# 1-Schematic_LP2951-xx_Matrix_Test_Board.net
KiCad netlist of a schematic drawn in EasyEDA
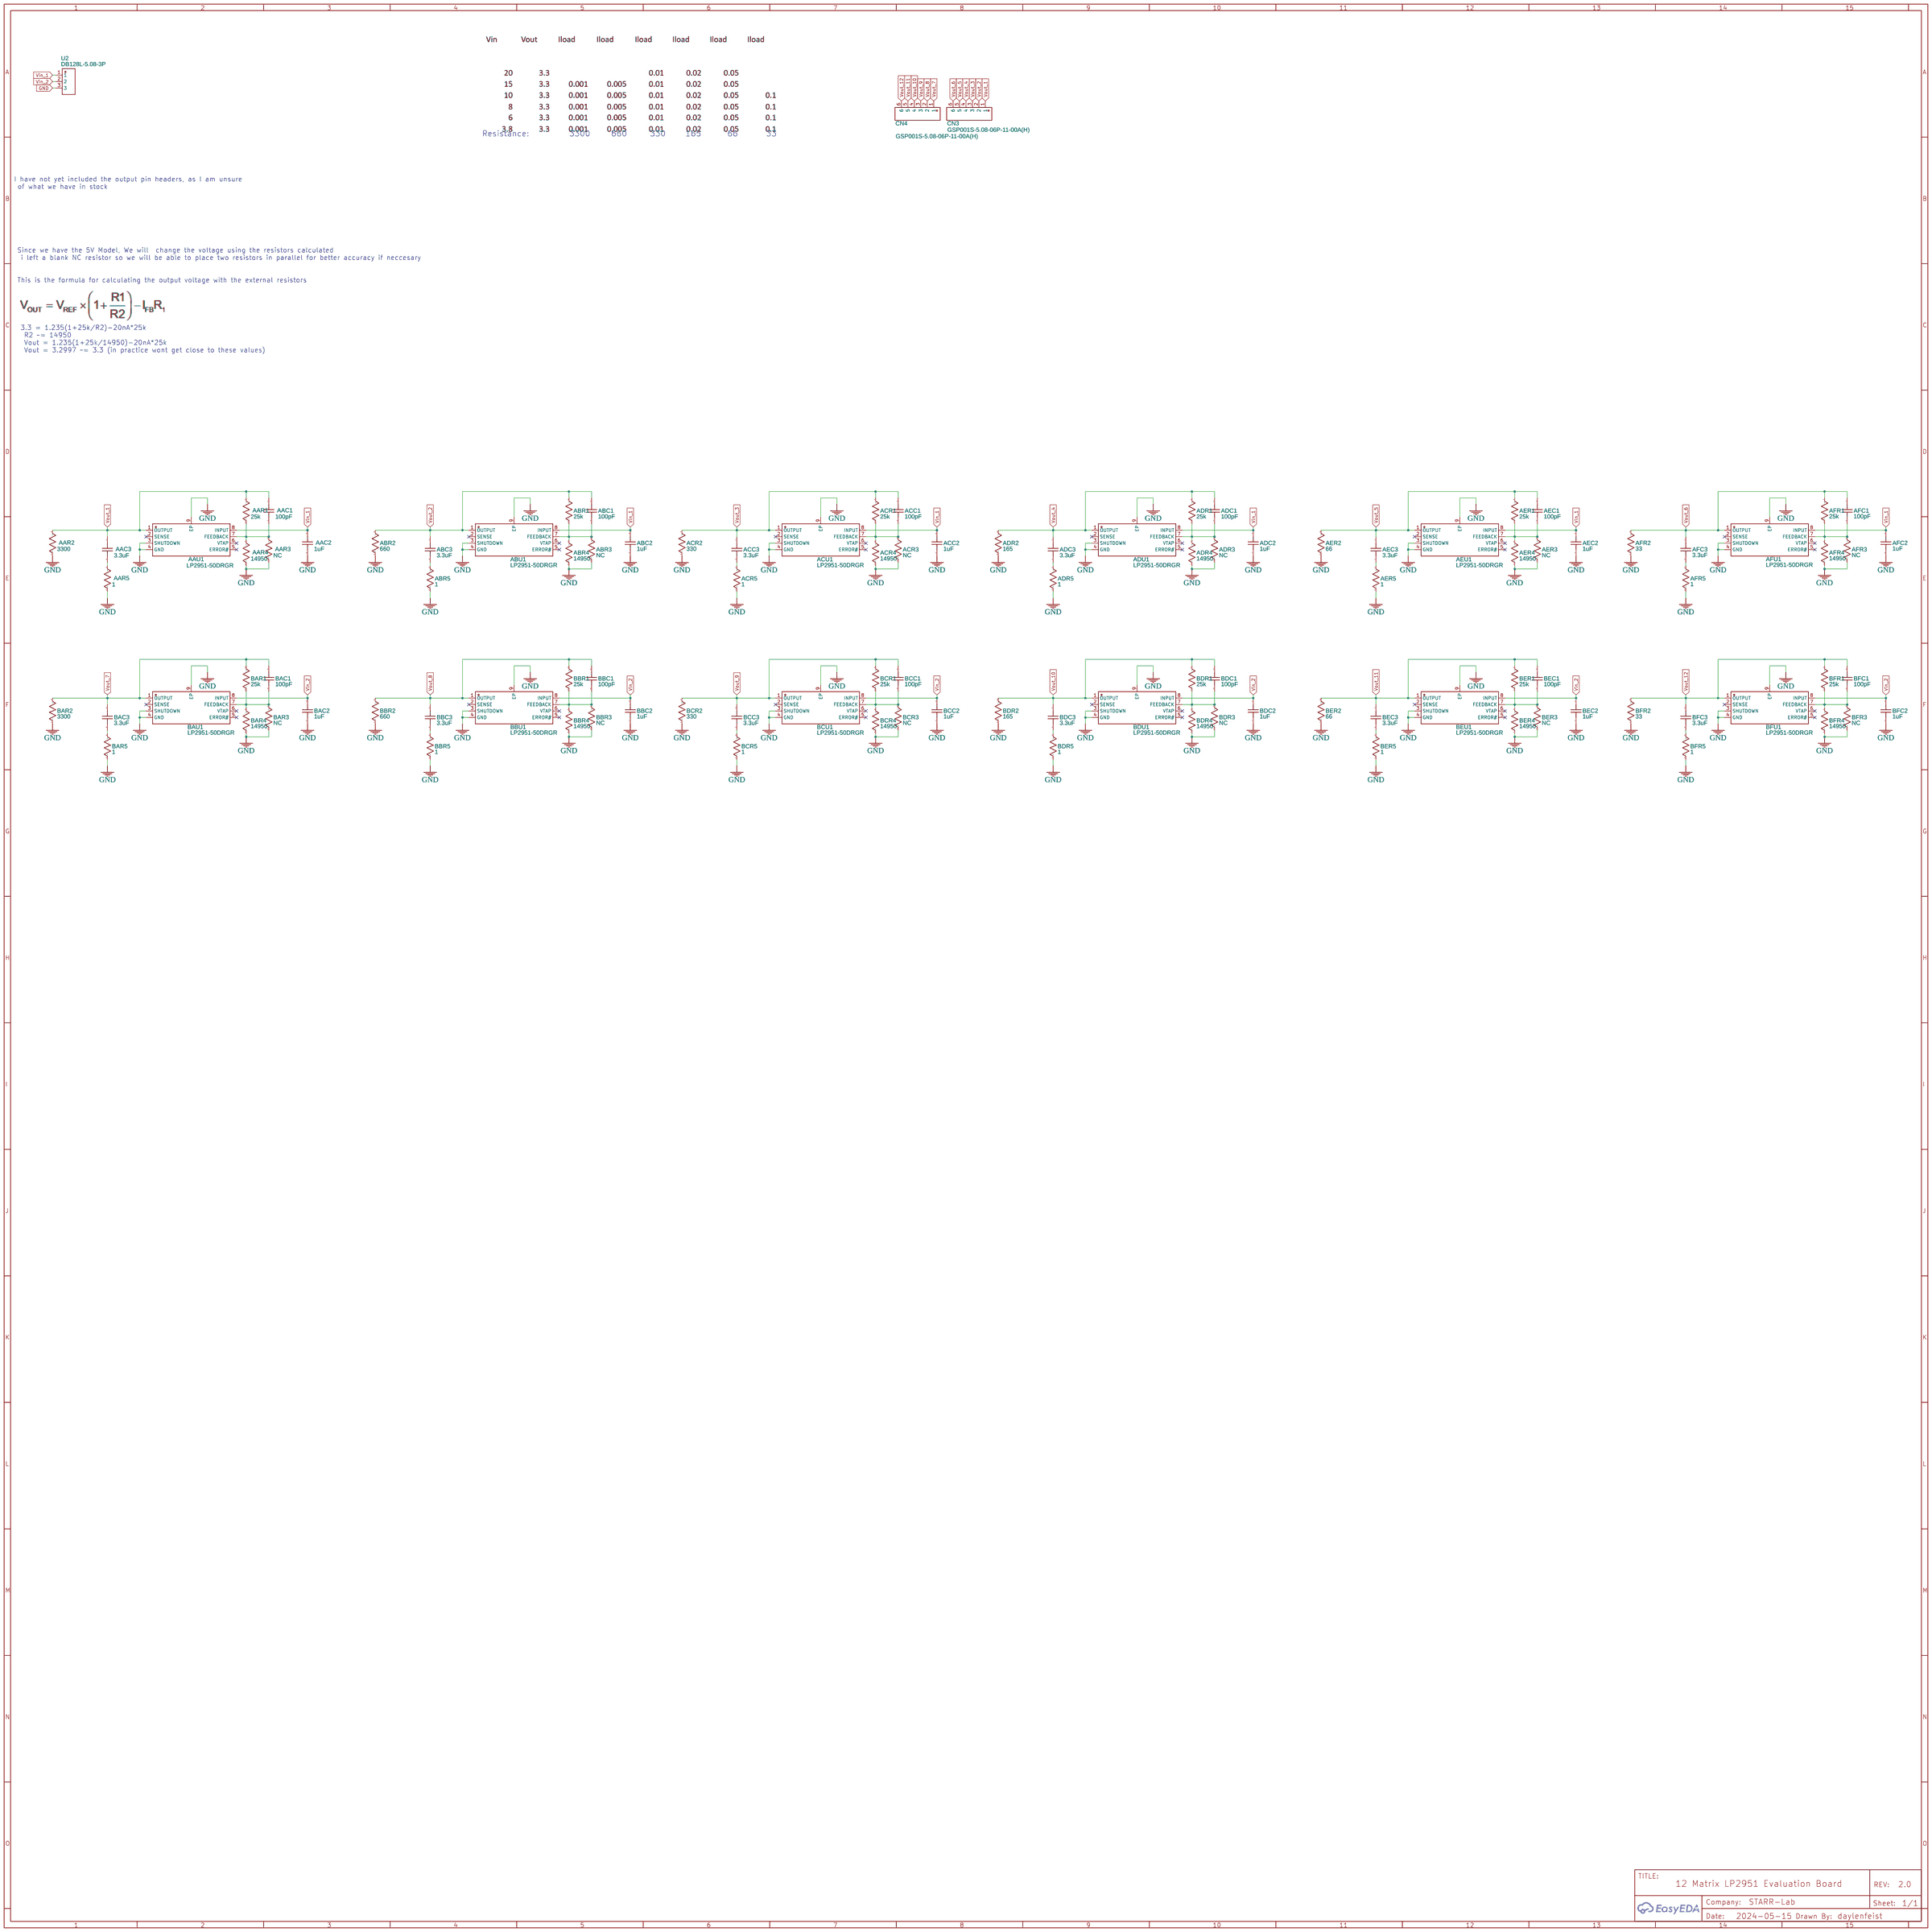
[diagram p0: schematic sheet]

(export (version "E")
  (design (tool "Eeschema 10.0.6"))
  (components
    (comp (ref "AAC1") (value "100pF") (libsource (lib "") (part "C_0603_US")))
    (comp (ref "AAC2") (value "1uF") (libsource (lib "") (part "C_0603_US_13")))
    (comp (ref "AAC3") (value "3.3uF") (libsource (lib "") (part "C_0603_US")))
    (comp (ref "AAR1") (value "25k") (libsource (lib "") (part "R_0603_US_11")))
    (comp (ref "AAR2") (value "3300") (libsource (lib "") (part "R_0603_US_11")))
    (comp (ref "AAR3") (value "NC") (libsource (lib "") (part "R_0603_US_11")))
    (comp (ref "AAR4") (value "14950") (libsource (lib "") (part "R_0603_US_11")))
    (comp (ref "AAR5") (value "1") (libsource (lib "") (part "R_0603_US_11")))
    (comp (ref "AAU1")
      (value "LP2951-50DRGR")
      (fields (field (name "Manufacturer") "TI(德州仪器)"))
      (libsource (lib "") (part "LP2951-50DRGR_1"))
    )
    (comp (ref "ABC1") (value "100pF") (libsource (lib "") (part "C_0603_US_10")))
    (comp (ref "ABC2") (value "1uF") (libsource (lib "") (part "C_0603_US_23")))
    (comp (ref "ABC3") (value "3.3uF") (libsource (lib "") (part "C_0603_US_10")))
    (comp (ref "ABR1") (value "25k") (libsource (lib "") (part "R_0603_US")))
    (comp (ref "ABR2") (value "660") (libsource (lib "") (part "R_0603_US")))
    (comp (ref "ABR3") (value "NC") (libsource (lib "") (part "R_0603_US")))
    (comp (ref "ABR4") (value "14950") (libsource (lib "") (part "R_0603_US")))
    (comp (ref "ABR5") (value "1") (libsource (lib "") (part "R_0603_US")))
    (comp (ref "ABU1")
      (value "LP2951-50DRGR")
      (fields (field (name "Manufacturer") "TI(德州仪器)"))
      (libsource (lib "") (part "LP2951-50DRGR"))
    )
    (comp (ref "ACC1") (value "100pF") (libsource (lib "") (part "C_0603_US_2")))
    (comp (ref "ACC2") (value "1uF") (libsource (lib "") (part "C_0603_US_3")))
    (comp (ref "ACC3") (value "3.3uF") (libsource (lib "") (part "C_0603_US_2")))
    (comp (ref "ACR1") (value "25k") (libsource (lib "") (part "R_0603_US_5")))
    (comp (ref "ACR2") (value "330") (libsource (lib "") (part "R_0603_US_5")))
    (comp (ref "ACR3") (value "NC") (libsource (lib "") (part "R_0603_US_5")))
    (comp (ref "ACR4") (value "14950") (libsource (lib "") (part "R_0603_US_5")))
    (comp (ref "ACR5") (value "1") (libsource (lib "") (part "R_0603_US_5")))
    (comp (ref "ACU1")
      (value "LP2951-50DRGR")
      (fields (field (name "Manufacturer") "TI(德州仪器)"))
      (libsource (lib "") (part "LP2951-50DRGR_5"))
    )
    (comp (ref "ADC1") (value "100pF") (libsource (lib "") (part "C_0603_US_1")))
    (comp (ref "ADC2") (value "1uF") (libsource (lib "") (part "C_0603_US_12")))
    (comp (ref "ADC3") (value "3.3uF") (libsource (lib "") (part "C_0603_US_1")))
    (comp (ref "ADR1") (value "25k") (libsource (lib "") (part "R_0603_US_10")))
    (comp (ref "ADR2") (value "165") (libsource (lib "") (part "R_0603_US_10")))
    (comp (ref "ADR3") (value "NC") (libsource (lib "") (part "R_0603_US_10")))
    (comp (ref "ADR4") (value "14950") (libsource (lib "") (part "R_0603_US_10")))
    (comp (ref "ADR5") (value "1") (libsource (lib "") (part "R_0603_US_10")))
    (comp (ref "ADU1")
      (value "LP2951-50DRGR")
      (fields (field (name "Manufacturer") "TI(德州仪器)"))
      (libsource (lib "") (part "LP2951-50DRGR_4"))
    )
    (comp (ref "AEC1") (value "100pF") (libsource (lib "") (part "C_0603_US_11")))
    (comp (ref "AEC2") (value "1uF") (libsource (lib "") (part "C_0603_US_18")))
    (comp (ref "AEC3") (value "3.3uF") (libsource (lib "") (part "C_0603_US_11")))
    (comp (ref "AER1") (value "25k") (libsource (lib "") (part "R_0603_US_8")))
    (comp (ref "AER2") (value "66") (libsource (lib "") (part "R_0603_US_8")))
    (comp (ref "AER3") (value "NC") (libsource (lib "") (part "R_0603_US_8")))
    (comp (ref "AER4") (value "14950") (libsource (lib "") (part "R_0603_US_8")))
    (comp (ref "AER5") (value "1") (libsource (lib "") (part "R_0603_US_8")))
    (comp (ref "AEU1")
      (value "LP2951-50DRGR")
      (fields (field (name "Manufacturer") "TI(德州仪器)"))
      (libsource (lib "") (part "LP2951-50DRGR_3"))
    )
    (comp (ref "AFC1") (value "100pF") (libsource (lib "") (part "C_0603_US_6")))
    (comp (ref "AFC2") (value "1uF") (libsource (lib "") (part "C_0603_US_22")))
    (comp (ref "AFC3") (value "3.3uF") (libsource (lib "") (part "C_0603_US_6")))
    (comp (ref "AFR1") (value "25k") (libsource (lib "") (part "R_0603_US_3")))
    (comp (ref "AFR2") (value "33") (libsource (lib "") (part "R_0603_US_3")))
    (comp (ref "AFR3") (value "NC") (libsource (lib "") (part "R_0603_US_3")))
    (comp (ref "AFR4") (value "14950") (libsource (lib "") (part "R_0603_US_3")))
    (comp (ref "AFR5") (value "1") (libsource (lib "") (part "R_0603_US_3")))
    (comp (ref "AFU1")
      (value "LP2951-50DRGR")
      (fields (field (name "Manufacturer") "TI(德州仪器)"))
      (libsource (lib "") (part "LP2951-50DRGR_8"))
    )
    (comp (ref "BAC1") (value "100pF") (libsource (lib "") (part "C_0603_US_9")))
    (comp (ref "BAC2") (value "1uF") (libsource (lib "") (part "C_0603_US_17")))
    (comp (ref "BAC3") (value "3.3uF") (libsource (lib "") (part "C_0603_US_9")))
    (comp (ref "BAR1") (value "25k") (libsource (lib "") (part "R_0603_US_6")))
    (comp (ref "BAR2") (value "3300") (libsource (lib "") (part "R_0603_US_6")))
    (comp (ref "BAR3") (value "NC") (libsource (lib "") (part "R_0603_US_6")))
    (comp (ref "BAR4") (value "14950") (libsource (lib "") (part "R_0603_US_6")))
    (comp (ref "BAR5") (value "1") (libsource (lib "") (part "R_0603_US_6")))
    (comp (ref "BAU1")
      (value "LP2951-50DRGR")
      (fields (field (name "Manufacturer") "TI(德州仪器)"))
      (libsource (lib "") (part "LP2951-50DRGR_9"))
    )
    (comp (ref "BBC1") (value "100pF") (libsource (lib "") (part "C_0603_US_7")))
    (comp (ref "BBC2") (value "1uF") (libsource (lib "") (part "C_0603_US_14")))
    (comp (ref "BBC3") (value "3.3uF") (libsource (lib "") (part "C_0603_US_7")))
    (comp (ref "BBR1") (value "25k") (libsource (lib "") (part "R_0603_US_4")))
    (comp (ref "BBR2") (value "660") (libsource (lib "") (part "R_0603_US_4")))
    (comp (ref "BBR3") (value "NC") (libsource (lib "") (part "R_0603_US_4")))
    (comp (ref "BBR4") (value "14950") (libsource (lib "") (part "R_0603_US_4")))
    (comp (ref "BBR5") (value "1") (libsource (lib "") (part "R_0603_US_4")))
    (comp (ref "BBU1")
      (value "LP2951-50DRGR")
      (fields (field (name "Manufacturer") "TI(德州仪器)"))
      (libsource (lib "") (part "LP2951-50DRGR_7"))
    )
    (comp (ref "BCC1") (value "100pF") (libsource (lib "") (part "C_0603_US_5")))
    (comp (ref "BCC2") (value "1uF") (libsource (lib "") (part "C_0603_US_21")))
    (comp (ref "BCC3") (value "3.3uF") (libsource (lib "") (part "C_0603_US_5")))
    (comp (ref "BCR1") (value "25k") (libsource (lib "") (part "R_0603_US_9")))
    (comp (ref "BCR2") (value "330") (libsource (lib "") (part "R_0603_US_9")))
    (comp (ref "BCR3") (value "NC") (libsource (lib "") (part "R_0603_US_9")))
    (comp (ref "BCR4") (value "14950") (libsource (lib "") (part "R_0603_US_9")))
    (comp (ref "BCR5") (value "1") (libsource (lib "") (part "R_0603_US_9")))
    (comp (ref "BCU1")
      (value "LP2951-50DRGR")
      (fields (field (name "Manufacturer") "TI(德州仪器)"))
      (libsource (lib "") (part "LP2951-50DRGR_11"))
    )
    (comp (ref "BDC1") (value "100pF") (libsource (lib "") (part "C_0603_US_4")))
    (comp (ref "BDC2") (value "1uF") (libsource (lib "") (part "C_0603_US_8")))
    (comp (ref "BDC3") (value "3.3uF") (libsource (lib "") (part "C_0603_US_4")))
    (comp (ref "BDR1") (value "25k") (libsource (lib "") (part "R_0603_US_2")))
    (comp (ref "BDR2") (value "165") (libsource (lib "") (part "R_0603_US_2")))
    (comp (ref "BDR3") (value "NC") (libsource (lib "") (part "R_0603_US_2")))
    (comp (ref "BDR4") (value "14950") (libsource (lib "") (part "R_0603_US_2")))
    (comp (ref "BDR5") (value "1") (libsource (lib "") (part "R_0603_US_2")))
    (comp (ref "BDU1")
      (value "LP2951-50DRGR")
      (fields (field (name "Manufacturer") "TI(德州仪器)"))
      (libsource (lib "") (part "LP2951-50DRGR_6"))
    )
    (comp (ref "BEC1") (value "100pF") (libsource (lib "") (part "C_0603_US_19")))
    (comp (ref "BEC2") (value "1uF") (libsource (lib "") (part "C_0603_US_15")))
    (comp (ref "BEC3") (value "3.3uF") (libsource (lib "") (part "C_0603_US_19")))
    (comp (ref "BER1") (value "25k") (libsource (lib "") (part "R_0603_US_1")))
    (comp (ref "BER2") (value "66") (libsource (lib "") (part "R_0603_US_1")))
    (comp (ref "BER3") (value "NC") (libsource (lib "") (part "R_0603_US_1")))
    (comp (ref "BER4") (value "14950") (libsource (lib "") (part "R_0603_US_1")))
    (comp (ref "BER5") (value "1") (libsource (lib "") (part "R_0603_US_1")))
    (comp (ref "BEU1")
      (value "LP2951-50DRGR")
      (fields (field (name "Manufacturer") "TI(德州仪器)"))
      (libsource (lib "") (part "LP2951-50DRGR_2"))
    )
    (comp (ref "BFC1") (value "100pF") (libsource (lib "") (part "C_0603_US_16")))
    (comp (ref "BFC2") (value "1uF") (libsource (lib "") (part "C_0603_US_20")))
    (comp (ref "BFC3") (value "3.3uF") (libsource (lib "") (part "C_0603_US_16")))
    (comp (ref "BFR1") (value "25k") (libsource (lib "") (part "R_0603_US_7")))
    (comp (ref "BFR2") (value "33") (libsource (lib "") (part "R_0603_US_7")))
    (comp (ref "BFR3") (value "NC") (libsource (lib "") (part "R_0603_US_7")))
    (comp (ref "BFR4") (value "14950") (libsource (lib "") (part "R_0603_US_7")))
    (comp (ref "BFR5") (value "1") (libsource (lib "") (part "R_0603_US_7")))
    (comp (ref "BFU1")
      (value "LP2951-50DRGR")
      (fields (field (name "Manufacturer") "TI(德州仪器)"))
      (libsource (lib "") (part "LP2951-50DRGR_10"))
    )
    (comp (ref "CN3")
      (value "GSP001S-5.08-06P-11-00A(H)")
      (fields (field (name "Manufacturer") "GOOSVN(高胜)"))
      (libsource (lib "") (part "GSP001S-5.08-06P-11-00A(H)"))
    )
    (comp (ref "CN4")
      (value "GSP001S-5.08-06P-11-00A(H)")
      (fields (field (name "Manufacturer") "GOOSVN(高胜)"))
      (libsource (lib "") (part "GSP001S-5.08-06P-11-00A(H)"))
    )
    (comp (ref "U2")
      (value "DB128L-5.08-3P")
      (fields
        (field (name "Manufacturer Part") "DB128L-5.08-3P-GN-S")
        (field (name "Manufacturer") "DORABO(地博电气)")
      )
      (libsource (lib "") (part "DB128L-5.08-3P"))
    )
  )
  (nets
    (net (code "1") (name "GND") (class "Default")
      (node (ref "AAC2") (pin "1") (pinfunction "1_1") (pintype "unspecified"))
      (node (ref "AAR2") (pin "1") (pinfunction "1_1") (pintype "unspecified"))
      (node (ref "AAR3") (pin "1") (pinfunction "1_1") (pintype "unspecified"))
      (node (ref "AAR4") (pin "1") (pinfunction "1_1") (pintype "unspecified"))
      (node (ref "AAR5") (pin "1") (pinfunction "1_1") (pintype "unspecified"))
      (node (ref "AAU1") (pin "3") (pinfunction "SHUTDOWN_3") (pintype "unspecified"))
      (node (ref "AAU1") (pin "4") (pinfunction "GND_4") (pintype "unspecified"))
      (node (ref "AAU1") (pin "9") (pinfunction "EP_9") (pintype "unspecified"))
      (node (ref "ABC2") (pin "1") (pinfunction "1_1") (pintype "unspecified"))
      (node (ref "ABR2") (pin "1") (pinfunction "1_1") (pintype "unspecified"))
      (node (ref "ABR3") (pin "1") (pinfunction "1_1") (pintype "unspecified"))
      (node (ref "ABR4") (pin "1") (pinfunction "1_1") (pintype "unspecified"))
      (node (ref "ABR5") (pin "1") (pinfunction "1_1") (pintype "unspecified"))
      (node (ref "ABU1") (pin "3") (pinfunction "SHUTDOWN_3") (pintype "unspecified"))
      (node (ref "ABU1") (pin "4") (pinfunction "GND_4") (pintype "unspecified"))
      (node (ref "ABU1") (pin "9") (pinfunction "EP_9") (pintype "unspecified"))
      (node (ref "ACC2") (pin "1") (pinfunction "1_1") (pintype "unspecified"))
      (node (ref "ACR2") (pin "1") (pinfunction "1_1") (pintype "unspecified"))
      (node (ref "ACR3") (pin "1") (pinfunction "1_1") (pintype "unspecified"))
      (node (ref "ACR4") (pin "1") (pinfunction "1_1") (pintype "unspecified"))
      (node (ref "ACR5") (pin "1") (pinfunction "1_1") (pintype "unspecified"))
      (node (ref "ACU1") (pin "3") (pinfunction "SHUTDOWN_3") (pintype "unspecified"))
      (node (ref "ACU1") (pin "4") (pinfunction "GND_4") (pintype "unspecified"))
      (node (ref "ACU1") (pin "9") (pinfunction "EP_9") (pintype "unspecified"))
      (node (ref "ADC2") (pin "1") (pinfunction "1_1") (pintype "unspecified"))
      (node (ref "ADR2") (pin "1") (pinfunction "1_1") (pintype "unspecified"))
      (node (ref "ADR3") (pin "1") (pinfunction "1_1") (pintype "unspecified"))
      (node (ref "ADR4") (pin "1") (pinfunction "1_1") (pintype "unspecified"))
      (node (ref "ADR5") (pin "1") (pinfunction "1_1") (pintype "unspecified"))
      (node (ref "ADU1") (pin "3") (pinfunction "SHUTDOWN_3") (pintype "unspecified"))
      (node (ref "ADU1") (pin "4") (pinfunction "GND_4") (pintype "unspecified"))
      (node (ref "ADU1") (pin "9") (pinfunction "EP_9") (pintype "unspecified"))
      (node (ref "AEC2") (pin "1") (pinfunction "1_1") (pintype "unspecified"))
      (node (ref "AER2") (pin "1") (pinfunction "1_1") (pintype "unspecified"))
      (node (ref "AER3") (pin "1") (pinfunction "1_1") (pintype "unspecified"))
      (node (ref "AER4") (pin "1") (pinfunction "1_1") (pintype "unspecified"))
      (node (ref "AER5") (pin "1") (pinfunction "1_1") (pintype "unspecified"))
      (node (ref "AEU1") (pin "3") (pinfunction "SHUTDOWN_3") (pintype "unspecified"))
      (node (ref "AEU1") (pin "4") (pinfunction "GND_4") (pintype "unspecified"))
      (node (ref "AEU1") (pin "9") (pinfunction "EP_9") (pintype "unspecified"))
      (node (ref "AFC2") (pin "1") (pinfunction "1_1") (pintype "unspecified"))
      (node (ref "AFR2") (pin "1") (pinfunction "1_1") (pintype "unspecified"))
      (node (ref "AFR3") (pin "1") (pinfunction "1_1") (pintype "unspecified"))
      (node (ref "AFR4") (pin "1") (pinfunction "1_1") (pintype "unspecified"))
      (node (ref "AFR5") (pin "1") (pinfunction "1_1") (pintype "unspecified"))
      (node (ref "AFU1") (pin "3") (pinfunction "SHUTDOWN_3") (pintype "unspecified"))
      (node (ref "AFU1") (pin "4") (pinfunction "GND_4") (pintype "unspecified"))
      (node (ref "AFU1") (pin "9") (pinfunction "EP_9") (pintype "unspecified"))
      (node (ref "BAC2") (pin "1") (pinfunction "1_1") (pintype "unspecified"))
      (node (ref "BAR2") (pin "1") (pinfunction "1_1") (pintype "unspecified"))
      (node (ref "BAR3") (pin "1") (pinfunction "1_1") (pintype "unspecified"))
      (node (ref "BAR4") (pin "1") (pinfunction "1_1") (pintype "unspecified"))
      (node (ref "BAR5") (pin "1") (pinfunction "1_1") (pintype "unspecified"))
      (node (ref "BAU1") (pin "3") (pinfunction "SHUTDOWN_3") (pintype "unspecified"))
      (node (ref "BAU1") (pin "4") (pinfunction "GND_4") (pintype "unspecified"))
      (node (ref "BAU1") (pin "9") (pinfunction "EP_9") (pintype "unspecified"))
      (node (ref "BBC2") (pin "1") (pinfunction "1_1") (pintype "unspecified"))
      (node (ref "BBR2") (pin "1") (pinfunction "1_1") (pintype "unspecified"))
      (node (ref "BBR3") (pin "1") (pinfunction "1_1") (pintype "unspecified"))
      (node (ref "BBR4") (pin "1") (pinfunction "1_1") (pintype "unspecified"))
      (node (ref "BBR5") (pin "1") (pinfunction "1_1") (pintype "unspecified"))
      (node (ref "BBU1") (pin "3") (pinfunction "SHUTDOWN_3") (pintype "unspecified"))
      (node (ref "BBU1") (pin "4") (pinfunction "GND_4") (pintype "unspecified"))
      (node (ref "BBU1") (pin "9") (pinfunction "EP_9") (pintype "unspecified"))
      (node (ref "BCC2") (pin "1") (pinfunction "1_1") (pintype "unspecified"))
      (node (ref "BCR2") (pin "1") (pinfunction "1_1") (pintype "unspecified"))
      (node (ref "BCR3") (pin "1") (pinfunction "1_1") (pintype "unspecified"))
      (node (ref "BCR4") (pin "1") (pinfunction "1_1") (pintype "unspecified"))
      (node (ref "BCR5") (pin "1") (pinfunction "1_1") (pintype "unspecified"))
      (node (ref "BCU1") (pin "3") (pinfunction "SHUTDOWN_3") (pintype "unspecified"))
      (node (ref "BCU1") (pin "4") (pinfunction "GND_4") (pintype "unspecified"))
      (node (ref "BCU1") (pin "9") (pinfunction "EP_9") (pintype "unspecified"))
      (node (ref "BDC2") (pin "1") (pinfunction "1_1") (pintype "unspecified"))
      (node (ref "BDR2") (pin "1") (pinfunction "1_1") (pintype "unspecified"))
      (node (ref "BDR3") (pin "1") (pinfunction "1_1") (pintype "unspecified"))
      (node (ref "BDR4") (pin "1") (pinfunction "1_1") (pintype "unspecified"))
      (node (ref "BDR5") (pin "1") (pinfunction "1_1") (pintype "unspecified"))
      (node (ref "BDU1") (pin "3") (pinfunction "SHUTDOWN_3") (pintype "unspecified"))
      (node (ref "BDU1") (pin "4") (pinfunction "GND_4") (pintype "unspecified"))
      (node (ref "BDU1") (pin "9") (pinfunction "EP_9") (pintype "unspecified"))
      (node (ref "BEC2") (pin "1") (pinfunction "1_1") (pintype "unspecified"))
      (node (ref "BER2") (pin "1") (pinfunction "1_1") (pintype "unspecified"))
      (node (ref "BER3") (pin "1") (pinfunction "1_1") (pintype "unspecified"))
      (node (ref "BER4") (pin "1") (pinfunction "1_1") (pintype "unspecified"))
      (node (ref "BER5") (pin "1") (pinfunction "1_1") (pintype "unspecified"))
      (node (ref "BEU1") (pin "3") (pinfunction "SHUTDOWN_3") (pintype "unspecified"))
      (node (ref "BEU1") (pin "4") (pinfunction "GND_4") (pintype "unspecified"))
      (node (ref "BEU1") (pin "9") (pinfunction "EP_9") (pintype "unspecified"))
      (node (ref "BFC2") (pin "1") (pinfunction "1_1") (pintype "unspecified"))
      (node (ref "BFR2") (pin "1") (pinfunction "1_1") (pintype "unspecified"))
      (node (ref "BFR3") (pin "1") (pinfunction "1_1") (pintype "unspecified"))
      (node (ref "BFR4") (pin "1") (pinfunction "1_1") (pintype "unspecified"))
      (node (ref "BFR5") (pin "1") (pinfunction "1_1") (pintype "unspecified"))
      (node (ref "BFU1") (pin "3") (pinfunction "SHUTDOWN_3") (pintype "unspecified"))
      (node (ref "BFU1") (pin "4") (pinfunction "GND_4") (pintype "unspecified"))
      (node (ref "BFU1") (pin "9") (pinfunction "EP_9") (pintype "unspecified"))
      (node (ref "U2") (pin "3") (pinfunction "3_3") (pintype "unspecified"))
    )
    (net (code "2") (name "Net-(AAC3-Pad2)") (class "Default")
      (node (ref "AAC3") (pin "2") (pinfunction "2_2") (pintype "unspecified"))
      (node (ref "AAR5") (pin "2") (pinfunction "2_2") (pintype "unspecified"))
    )
    (net (code "3") (name "Net-(AAU1-FEEDBACK)") (class "Default")
      (node (ref "AAC1") (pin "2") (pinfunction "2_2") (pintype "unspecified"))
      (node (ref "AAR1") (pin "1") (pinfunction "1_1") (pintype "unspecified"))
      (node (ref "AAR3") (pin "2") (pinfunction "2_2") (pintype "unspecified"))
      (node (ref "AAR4") (pin "2") (pinfunction "2_2") (pintype "unspecified"))
      (node (ref "AAU1") (pin "7") (pinfunction "FEEDBACK_7") (pintype "unspecified"))
    )
    (net (code "4") (name "Net-(ABC3-Pad2)") (class "Default")
      (node (ref "ABC3") (pin "2") (pinfunction "2_2") (pintype "unspecified"))
      (node (ref "ABR5") (pin "2") (pinfunction "2_2") (pintype "unspecified"))
    )
    (net (code "5") (name "Net-(ABU1-FEEDBACK)") (class "Default")
      (node (ref "ABC1") (pin "2") (pinfunction "2_2") (pintype "unspecified"))
      (node (ref "ABR1") (pin "1") (pinfunction "1_1") (pintype "unspecified"))
      (node (ref "ABR3") (pin "2") (pinfunction "2_2") (pintype "unspecified"))
      (node (ref "ABR4") (pin "2") (pinfunction "2_2") (pintype "unspecified"))
      (node (ref "ABU1") (pin "7") (pinfunction "FEEDBACK_7") (pintype "unspecified"))
    )
    (net (code "6") (name "Net-(ACC3-Pad2)") (class "Default")
      (node (ref "ACC3") (pin "2") (pinfunction "2_2") (pintype "unspecified"))
      (node (ref "ACR5") (pin "2") (pinfunction "2_2") (pintype "unspecified"))
    )
    (net (code "7") (name "Net-(ACU1-FEEDBACK)") (class "Default")
      (node (ref "ACC1") (pin "2") (pinfunction "2_2") (pintype "unspecified"))
      (node (ref "ACR1") (pin "1") (pinfunction "1_1") (pintype "unspecified"))
      (node (ref "ACR3") (pin "2") (pinfunction "2_2") (pintype "unspecified"))
      (node (ref "ACR4") (pin "2") (pinfunction "2_2") (pintype "unspecified"))
      (node (ref "ACU1") (pin "7") (pinfunction "FEEDBACK_7") (pintype "unspecified"))
    )
    (net (code "8") (name "Net-(ADC3-Pad2)") (class "Default")
      (node (ref "ADC3") (pin "2") (pinfunction "2_2") (pintype "unspecified"))
      (node (ref "ADR5") (pin "2") (pinfunction "2_2") (pintype "unspecified"))
    )
    (net (code "9") (name "Net-(ADU1-FEEDBACK)") (class "Default")
      (node (ref "ADC1") (pin "2") (pinfunction "2_2") (pintype "unspecified"))
      (node (ref "ADR1") (pin "1") (pinfunction "1_1") (pintype "unspecified"))
      (node (ref "ADR3") (pin "2") (pinfunction "2_2") (pintype "unspecified"))
      (node (ref "ADR4") (pin "2") (pinfunction "2_2") (pintype "unspecified"))
      (node (ref "ADU1") (pin "7") (pinfunction "FEEDBACK_7") (pintype "unspecified"))
    )
    (net (code "10") (name "Net-(AEC3-Pad2)") (class "Default")
      (node (ref "AEC3") (pin "2") (pinfunction "2_2") (pintype "unspecified"))
      (node (ref "AER5") (pin "2") (pinfunction "2_2") (pintype "unspecified"))
    )
    (net (code "11") (name "Net-(AEU1-FEEDBACK)") (class "Default")
      (node (ref "AEC1") (pin "2") (pinfunction "2_2") (pintype "unspecified"))
      (node (ref "AER1") (pin "1") (pinfunction "1_1") (pintype "unspecified"))
      (node (ref "AER3") (pin "2") (pinfunction "2_2") (pintype "unspecified"))
      (node (ref "AER4") (pin "2") (pinfunction "2_2") (pintype "unspecified"))
      (node (ref "AEU1") (pin "7") (pinfunction "FEEDBACK_7") (pintype "unspecified"))
    )
    (net (code "12") (name "Net-(AFC3-Pad2)") (class "Default")
      (node (ref "AFC3") (pin "2") (pinfunction "2_2") (pintype "unspecified"))
      (node (ref "AFR5") (pin "2") (pinfunction "2_2") (pintype "unspecified"))
    )
    (net (code "13") (name "Net-(AFU1-FEEDBACK)") (class "Default")
      (node (ref "AFC1") (pin "2") (pinfunction "2_2") (pintype "unspecified"))
      (node (ref "AFR1") (pin "1") (pinfunction "1_1") (pintype "unspecified"))
      (node (ref "AFR3") (pin "2") (pinfunction "2_2") (pintype "unspecified"))
      (node (ref "AFR4") (pin "2") (pinfunction "2_2") (pintype "unspecified"))
      (node (ref "AFU1") (pin "7") (pinfunction "FEEDBACK_7") (pintype "unspecified"))
    )
    (net (code "14") (name "Net-(BAC3-Pad2)") (class "Default")
      (node (ref "BAC3") (pin "2") (pinfunction "2_2") (pintype "unspecified"))
      (node (ref "BAR5") (pin "2") (pinfunction "2_2") (pintype "unspecified"))
    )
    (net (code "15") (name "Net-(BAU1-FEEDBACK)") (class "Default")
      (node (ref "BAC1") (pin "2") (pinfunction "2_2") (pintype "unspecified"))
      (node (ref "BAR1") (pin "1") (pinfunction "1_1") (pintype "unspecified"))
      (node (ref "BAR3") (pin "2") (pinfunction "2_2") (pintype "unspecified"))
      (node (ref "BAR4") (pin "2") (pinfunction "2_2") (pintype "unspecified"))
      (node (ref "BAU1") (pin "7") (pinfunction "FEEDBACK_7") (pintype "unspecified"))
    )
    (net (code "16") (name "Net-(BBC3-Pad2)") (class "Default")
      (node (ref "BBC3") (pin "2") (pinfunction "2_2") (pintype "unspecified"))
      (node (ref "BBR5") (pin "2") (pinfunction "2_2") (pintype "unspecified"))
    )
    (net (code "17") (name "Net-(BBU1-FEEDBACK)") (class "Default")
      (node (ref "BBC1") (pin "2") (pinfunction "2_2") (pintype "unspecified"))
      (node (ref "BBR1") (pin "1") (pinfunction "1_1") (pintype "unspecified"))
      (node (ref "BBR3") (pin "2") (pinfunction "2_2") (pintype "unspecified"))
      (node (ref "BBR4") (pin "2") (pinfunction "2_2") (pintype "unspecified"))
      (node (ref "BBU1") (pin "7") (pinfunction "FEEDBACK_7") (pintype "unspecified"))
    )
    (net (code "18") (name "Net-(BCC3-Pad2)") (class "Default")
      (node (ref "BCC3") (pin "2") (pinfunction "2_2") (pintype "unspecified"))
      (node (ref "BCR5") (pin "2") (pinfunction "2_2") (pintype "unspecified"))
    )
    (net (code "19") (name "Net-(BCU1-FEEDBACK)") (class "Default")
      (node (ref "BCC1") (pin "2") (pinfunction "2_2") (pintype "unspecified"))
      (node (ref "BCR1") (pin "1") (pinfunction "1_1") (pintype "unspecified"))
      (node (ref "BCR3") (pin "2") (pinfunction "2_2") (pintype "unspecified"))
      (node (ref "BCR4") (pin "2") (pinfunction "2_2") (pintype "unspecified"))
      (node (ref "BCU1") (pin "7") (pinfunction "FEEDBACK_7") (pintype "unspecified"))
    )
    (net (code "20") (name "Net-(BDC3-Pad2)") (class "Default")
      (node (ref "BDC3") (pin "2") (pinfunction "2_2") (pintype "unspecified"))
      (node (ref "BDR5") (pin "2") (pinfunction "2_2") (pintype "unspecified"))
    )
    (net (code "21") (name "Net-(BDU1-FEEDBACK)") (class "Default")
      (node (ref "BDC1") (pin "2") (pinfunction "2_2") (pintype "unspecified"))
      (node (ref "BDR1") (pin "1") (pinfunction "1_1") (pintype "unspecified"))
      (node (ref "BDR3") (pin "2") (pinfunction "2_2") (pintype "unspecified"))
      (node (ref "BDR4") (pin "2") (pinfunction "2_2") (pintype "unspecified"))
      (node (ref "BDU1") (pin "7") (pinfunction "FEEDBACK_7") (pintype "unspecified"))
    )
    (net (code "22") (name "Net-(BEC3-Pad2)") (class "Default")
      (node (ref "BEC3") (pin "2") (pinfunction "2_2") (pintype "unspecified"))
      (node (ref "BER5") (pin "2") (pinfunction "2_2") (pintype "unspecified"))
    )
    (net (code "23") (name "Net-(BEU1-FEEDBACK)") (class "Default")
      (node (ref "BEC1") (pin "2") (pinfunction "2_2") (pintype "unspecified"))
      (node (ref "BER1") (pin "1") (pinfunction "1_1") (pintype "unspecified"))
      (node (ref "BER3") (pin "2") (pinfunction "2_2") (pintype "unspecified"))
      (node (ref "BER4") (pin "2") (pinfunction "2_2") (pintype "unspecified"))
      (node (ref "BEU1") (pin "7") (pinfunction "FEEDBACK_7") (pintype "unspecified"))
    )
    (net (code "24") (name "Net-(BFC3-Pad2)") (class "Default")
      (node (ref "BFC3") (pin "2") (pinfunction "2_2") (pintype "unspecified"))
      (node (ref "BFR5") (pin "2") (pinfunction "2_2") (pintype "unspecified"))
    )
    (net (code "25") (name "Net-(BFU1-FEEDBACK)") (class "Default")
      (node (ref "BFC1") (pin "2") (pinfunction "2_2") (pintype "unspecified"))
      (node (ref "BFR1") (pin "1") (pinfunction "1_1") (pintype "unspecified"))
      (node (ref "BFR3") (pin "2") (pinfunction "2_2") (pintype "unspecified"))
      (node (ref "BFR4") (pin "2") (pinfunction "2_2") (pintype "unspecified"))
      (node (ref "BFU1") (pin "7") (pinfunction "FEEDBACK_7") (pintype "unspecified"))
    )
    (net (code "26") (name "Vin_1") (class "Default")
      (node (ref "AAC2") (pin "2") (pinfunction "2_2") (pintype "unspecified"))
      (node (ref "AAU1") (pin "8") (pinfunction "INPUT_8") (pintype "unspecified"))
      (node (ref "ABC2") (pin "2") (pinfunction "2_2") (pintype "unspecified"))
      (node (ref "ABU1") (pin "8") (pinfunction "INPUT_8") (pintype "unspecified"))
      (node (ref "ACC2") (pin "2") (pinfunction "2_2") (pintype "unspecified"))
      (node (ref "ACU1") (pin "8") (pinfunction "INPUT_8") (pintype "unspecified"))
      (node (ref "ADC2") (pin "2") (pinfunction "2_2") (pintype "unspecified"))
      (node (ref "ADU1") (pin "8") (pinfunction "INPUT_8") (pintype "unspecified"))
      (node (ref "AEC2") (pin "2") (pinfunction "2_2") (pintype "unspecified"))
      (node (ref "AEU1") (pin "8") (pinfunction "INPUT_8") (pintype "unspecified"))
      (node (ref "AFC2") (pin "2") (pinfunction "2_2") (pintype "unspecified"))
      (node (ref "AFU1") (pin "8") (pinfunction "INPUT_8") (pintype "unspecified"))
      (node (ref "U2") (pin "1") (pinfunction "1_1") (pintype "unspecified"))
    )
    (net (code "27") (name "Vin_2") (class "Default")
      (node (ref "BAC2") (pin "2") (pinfunction "2_2") (pintype "unspecified"))
      (node (ref "BAU1") (pin "8") (pinfunction "INPUT_8") (pintype "unspecified"))
      (node (ref "BBC2") (pin "2") (pinfunction "2_2") (pintype "unspecified"))
      (node (ref "BBU1") (pin "8") (pinfunction "INPUT_8") (pintype "unspecified"))
      (node (ref "BCC2") (pin "2") (pinfunction "2_2") (pintype "unspecified"))
      (node (ref "BCU1") (pin "8") (pinfunction "INPUT_8") (pintype "unspecified"))
      (node (ref "BDC2") (pin "2") (pinfunction "2_2") (pintype "unspecified"))
      (node (ref "BDU1") (pin "8") (pinfunction "INPUT_8") (pintype "unspecified"))
      (node (ref "BEC2") (pin "2") (pinfunction "2_2") (pintype "unspecified"))
      (node (ref "BEU1") (pin "8") (pinfunction "INPUT_8") (pintype "unspecified"))
      (node (ref "BFC2") (pin "2") (pinfunction "2_2") (pintype "unspecified"))
      (node (ref "BFU1") (pin "8") (pinfunction "INPUT_8") (pintype "unspecified"))
      (node (ref "U2") (pin "2") (pinfunction "2_2") (pintype "unspecified"))
    )
    (net (code "28") (name "Vout_1") (class "Default")
      (node (ref "AAC1") (pin "1") (pinfunction "1_1") (pintype "unspecified"))
      (node (ref "AAC3") (pin "1") (pinfunction "1_1") (pintype "unspecified"))
      (node (ref "AAR1") (pin "2") (pinfunction "2_2") (pintype "unspecified"))
      (node (ref "AAR2") (pin "2") (pinfunction "2_2") (pintype "unspecified"))
      (node (ref "AAU1") (pin "1") (pinfunction "OUTPUT_1") (pintype "unspecified"))
      (node (ref "CN3") (pin "1") (pinfunction "1_1") (pintype "unspecified"))
    )
    (net (code "29") (name "Vout_2") (class "Default")
      (node (ref "ABC1") (pin "1") (pinfunction "1_1") (pintype "unspecified"))
      (node (ref "ABC3") (pin "1") (pinfunction "1_1") (pintype "unspecified"))
      (node (ref "ABR1") (pin "2") (pinfunction "2_2") (pintype "unspecified"))
      (node (ref "ABR2") (pin "2") (pinfunction "2_2") (pintype "unspecified"))
      (node (ref "ABU1") (pin "1") (pinfunction "OUTPUT_1") (pintype "unspecified"))
      (node (ref "CN3") (pin "2") (pinfunction "2_2") (pintype "unspecified"))
    )
    (net (code "30") (name "Vout_3") (class "Default")
      (node (ref "ACC1") (pin "1") (pinfunction "1_1") (pintype "unspecified"))
      (node (ref "ACC3") (pin "1") (pinfunction "1_1") (pintype "unspecified"))
      (node (ref "ACR1") (pin "2") (pinfunction "2_2") (pintype "unspecified"))
      (node (ref "ACR2") (pin "2") (pinfunction "2_2") (pintype "unspecified"))
      (node (ref "ACU1") (pin "1") (pinfunction "OUTPUT_1") (pintype "unspecified"))
      (node (ref "CN3") (pin "3") (pinfunction "3_3") (pintype "unspecified"))
    )
    (net (code "31") (name "Vout_4") (class "Default")
      (node (ref "ADC1") (pin "1") (pinfunction "1_1") (pintype "unspecified"))
      (node (ref "ADC3") (pin "1") (pinfunction "1_1") (pintype "unspecified"))
      (node (ref "ADR1") (pin "2") (pinfunction "2_2") (pintype "unspecified"))
      (node (ref "ADR2") (pin "2") (pinfunction "2_2") (pintype "unspecified"))
      (node (ref "ADU1") (pin "1") (pinfunction "OUTPUT_1") (pintype "unspecified"))
      (node (ref "CN3") (pin "4") (pinfunction "4_4") (pintype "unspecified"))
    )
    (net (code "32") (name "Vout_5") (class "Default")
      (node (ref "AEC1") (pin "1") (pinfunction "1_1") (pintype "unspecified"))
      (node (ref "AEC3") (pin "1") (pinfunction "1_1") (pintype "unspecified"))
      (node (ref "AER1") (pin "2") (pinfunction "2_2") (pintype "unspecified"))
      (node (ref "AER2") (pin "2") (pinfunction "2_2") (pintype "unspecified"))
      (node (ref "AEU1") (pin "1") (pinfunction "OUTPUT_1") (pintype "unspecified"))
      (node (ref "CN3") (pin "5") (pinfunction "5_5") (pintype "unspecified"))
    )
    (net (code "33") (name "Vout_6") (class "Default")
      (node (ref "AFC1") (pin "1") (pinfunction "1_1") (pintype "unspecified"))
      (node (ref "AFC3") (pin "1") (pinfunction "1_1") (pintype "unspecified"))
      (node (ref "AFR1") (pin "2") (pinfunction "2_2") (pintype "unspecified"))
      (node (ref "AFR2") (pin "2") (pinfunction "2_2") (pintype "unspecified"))
      (node (ref "AFU1") (pin "1") (pinfunction "OUTPUT_1") (pintype "unspecified"))
      (node (ref "CN3") (pin "6") (pinfunction "6_6") (pintype "unspecified"))
    )
    (net (code "34") (name "Vout_7") (class "Default")
      (node (ref "BAC1") (pin "1") (pinfunction "1_1") (pintype "unspecified"))
      (node (ref "BAC3") (pin "1") (pinfunction "1_1") (pintype "unspecified"))
      (node (ref "BAR1") (pin "2") (pinfunction "2_2") (pintype "unspecified"))
      (node (ref "BAR2") (pin "2") (pinfunction "2_2") (pintype "unspecified"))
      (node (ref "BAU1") (pin "1") (pinfunction "OUTPUT_1") (pintype "unspecified"))
      (node (ref "CN4") (pin "1") (pinfunction "1_1") (pintype "unspecified"))
    )
    (net (code "35") (name "Vout_8") (class "Default")
      (node (ref "BBC1") (pin "1") (pinfunction "1_1") (pintype "unspecified"))
      (node (ref "BBC3") (pin "1") (pinfunction "1_1") (pintype "unspecified"))
      (node (ref "BBR1") (pin "2") (pinfunction "2_2") (pintype "unspecified"))
      (node (ref "BBR2") (pin "2") (pinfunction "2_2") (pintype "unspecified"))
      (node (ref "BBU1") (pin "1") (pinfunction "OUTPUT_1") (pintype "unspecified"))
      (node (ref "CN4") (pin "2") (pinfunction "2_2") (pintype "unspecified"))
    )
    (net (code "36") (name "Vout_9") (class "Default")
      (node (ref "BCC1") (pin "1") (pinfunction "1_1") (pintype "unspecified"))
      (node (ref "BCC3") (pin "1") (pinfunction "1_1") (pintype "unspecified"))
      (node (ref "BCR1") (pin "2") (pinfunction "2_2") (pintype "unspecified"))
      (node (ref "BCR2") (pin "2") (pinfunction "2_2") (pintype "unspecified"))
      (node (ref "BCU1") (pin "1") (pinfunction "OUTPUT_1") (pintype "unspecified"))
      (node (ref "CN4") (pin "3") (pinfunction "3_3") (pintype "unspecified"))
    )
    (net (code "37") (name "Vout_10") (class "Default")
      (node (ref "BDC1") (pin "1") (pinfunction "1_1") (pintype "unspecified"))
      (node (ref "BDC3") (pin "1") (pinfunction "1_1") (pintype "unspecified"))
      (node (ref "BDR1") (pin "2") (pinfunction "2_2") (pintype "unspecified"))
      (node (ref "BDR2") (pin "2") (pinfunction "2_2") (pintype "unspecified"))
      (node (ref "BDU1") (pin "1") (pinfunction "OUTPUT_1") (pintype "unspecified"))
      (node (ref "CN4") (pin "4") (pinfunction "4_4") (pintype "unspecified"))
    )
    (net (code "38") (name "Vout_11") (class "Default")
      (node (ref "BEC1") (pin "1") (pinfunction "1_1") (pintype "unspecified"))
      (node (ref "BEC3") (pin "1") (pinfunction "1_1") (pintype "unspecified"))
      (node (ref "BER1") (pin "2") (pinfunction "2_2") (pintype "unspecified"))
      (node (ref "BER2") (pin "2") (pinfunction "2_2") (pintype "unspecified"))
      (node (ref "BEU1") (pin "1") (pinfunction "OUTPUT_1") (pintype "unspecified"))
      (node (ref "CN4") (pin "5") (pinfunction "5_5") (pintype "unspecified"))
    )
    (net (code "39") (name "Vout_12") (class "Default")
      (node (ref "BFC1") (pin "1") (pinfunction "1_1") (pintype "unspecified"))
      (node (ref "BFC3") (pin "1") (pinfunction "1_1") (pintype "unspecified"))
      (node (ref "BFR1") (pin "2") (pinfunction "2_2") (pintype "unspecified"))
      (node (ref "BFR2") (pin "2") (pinfunction "2_2") (pintype "unspecified"))
      (node (ref "BFU1") (pin "1") (pinfunction "OUTPUT_1") (pintype "unspecified"))
      (node (ref "CN4") (pin "6") (pinfunction "6_6") (pintype "unspecified"))
    )
    (net (code "40") (name "unconnected-(AAU1-ERROR#-Pad5)") (class "Default")
      (node (ref "AAU1") (pin "5") (pinfunction "ERROR#_5") (pintype "unspecified+no_connect"))
    )
    (net (code "41") (name "unconnected-(AAU1-SENSE-Pad2)") (class "Default")
      (node (ref "AAU1") (pin "2") (pinfunction "SENSE_2") (pintype "unspecified+no_connect"))
    )
    (net (code "42") (name "unconnected-(AAU1-VTAP-Pad6)") (class "Default")
      (node (ref "AAU1") (pin "6") (pinfunction "VTAP_6") (pintype "unspecified+no_connect"))
    )
    (net (code "43") (name "unconnected-(ABU1-ERROR#-Pad5)") (class "Default")
      (node (ref "ABU1") (pin "5") (pinfunction "ERROR#_5") (pintype "unspecified+no_connect"))
    )
    (net (code "44") (name "unconnected-(ABU1-SENSE-Pad2)") (class "Default")
      (node (ref "ABU1") (pin "2") (pinfunction "SENSE_2") (pintype "unspecified+no_connect"))
    )
    (net (code "45") (name "unconnected-(ABU1-VTAP-Pad6)") (class "Default")
      (node (ref "ABU1") (pin "6") (pinfunction "VTAP_6") (pintype "unspecified+no_connect"))
    )
    (net (code "46") (name "unconnected-(ACU1-ERROR#-Pad5)") (class "Default")
      (node (ref "ACU1") (pin "5") (pinfunction "ERROR#_5") (pintype "unspecified+no_connect"))
    )
    (net (code "47") (name "unconnected-(ACU1-SENSE-Pad2)") (class "Default")
      (node (ref "ACU1") (pin "2") (pinfunction "SENSE_2") (pintype "unspecified+no_connect"))
    )
    (net (code "48") (name "unconnected-(ACU1-VTAP-Pad6)") (class "Default")
      (node (ref "ACU1") (pin "6") (pinfunction "VTAP_6") (pintype "unspecified+no_connect"))
    )
    (net (code "49") (name "unconnected-(ADU1-ERROR#-Pad5)") (class "Default")
      (node (ref "ADU1") (pin "5") (pinfunction "ERROR#_5") (pintype "unspecified+no_connect"))
    )
    (net (code "50") (name "unconnected-(ADU1-SENSE-Pad2)") (class "Default")
      (node (ref "ADU1") (pin "2") (pinfunction "SENSE_2") (pintype "unspecified+no_connect"))
    )
    (net (code "51") (name "unconnected-(ADU1-VTAP-Pad6)") (class "Default")
      (node (ref "ADU1") (pin "6") (pinfunction "VTAP_6") (pintype "unspecified+no_connect"))
    )
    (net (code "52") (name "unconnected-(AEU1-ERROR#-Pad5)") (class "Default")
      (node (ref "AEU1") (pin "5") (pinfunction "ERROR#_5") (pintype "unspecified+no_connect"))
    )
    (net (code "53") (name "unconnected-(AEU1-SENSE-Pad2)") (class "Default")
      (node (ref "AEU1") (pin "2") (pinfunction "SENSE_2") (pintype "unspecified+no_connect"))
    )
    (net (code "54") (name "unconnected-(AEU1-VTAP-Pad6)") (class "Default")
      (node (ref "AEU1") (pin "6") (pinfunction "VTAP_6") (pintype "unspecified+no_connect"))
    )
    (net (code "55") (name "unconnected-(AFU1-ERROR#-Pad5)") (class "Default")
      (node (ref "AFU1") (pin "5") (pinfunction "ERROR#_5") (pintype "unspecified+no_connect"))
    )
    (net (code "56") (name "unconnected-(AFU1-SENSE-Pad2)") (class "Default")
      (node (ref "AFU1") (pin "2") (pinfunction "SENSE_2") (pintype "unspecified+no_connect"))
    )
    (net (code "57") (name "unconnected-(AFU1-VTAP-Pad6)") (class "Default")
      (node (ref "AFU1") (pin "6") (pinfunction "VTAP_6") (pintype "unspecified+no_connect"))
    )
    (net (code "58") (name "unconnected-(BAU1-ERROR#-Pad5)") (class "Default")
      (node (ref "BAU1") (pin "5") (pinfunction "ERROR#_5") (pintype "unspecified+no_connect"))
    )
    (net (code "59") (name "unconnected-(BAU1-SENSE-Pad2)") (class "Default")
      (node (ref "BAU1") (pin "2") (pinfunction "SENSE_2") (pintype "unspecified+no_connect"))
    )
    (net (code "60") (name "unconnected-(BAU1-VTAP-Pad6)") (class "Default")
      (node (ref "BAU1") (pin "6") (pinfunction "VTAP_6") (pintype "unspecified+no_connect"))
    )
    (net (code "61") (name "unconnected-(BBU1-ERROR#-Pad5)") (class "Default")
      (node (ref "BBU1") (pin "5") (pinfunction "ERROR#_5") (pintype "unspecified+no_connect"))
    )
    (net (code "62") (name "unconnected-(BBU1-SENSE-Pad2)") (class "Default")
      (node (ref "BBU1") (pin "2") (pinfunction "SENSE_2") (pintype "unspecified+no_connect"))
    )
    (net (code "63") (name "unconnected-(BBU1-VTAP-Pad6)") (class "Default")
      (node (ref "BBU1") (pin "6") (pinfunction "VTAP_6") (pintype "unspecified+no_connect"))
    )
    (net (code "64") (name "unconnected-(BCU1-ERROR#-Pad5)") (class "Default")
      (node (ref "BCU1") (pin "5") (pinfunction "ERROR#_5") (pintype "unspecified+no_connect"))
    )
    (net (code "65") (name "unconnected-(BCU1-SENSE-Pad2)") (class "Default")
      (node (ref "BCU1") (pin "2") (pinfunction "SENSE_2") (pintype "unspecified+no_connect"))
    )
    (net (code "66") (name "unconnected-(BCU1-VTAP-Pad6)") (class "Default")
      (node (ref "BCU1") (pin "6") (pinfunction "VTAP_6") (pintype "unspecified+no_connect"))
    )
    (net (code "67") (name "unconnected-(BDU1-ERROR#-Pad5)") (class "Default")
      (node (ref "BDU1") (pin "5") (pinfunction "ERROR#_5") (pintype "unspecified+no_connect"))
    )
    (net (code "68") (name "unconnected-(BDU1-SENSE-Pad2)") (class "Default")
      (node (ref "BDU1") (pin "2") (pinfunction "SENSE_2") (pintype "unspecified+no_connect"))
    )
    (net (code "69") (name "unconnected-(BDU1-VTAP-Pad6)") (class "Default")
      (node (ref "BDU1") (pin "6") (pinfunction "VTAP_6") (pintype "unspecified+no_connect"))
    )
    (net (code "70") (name "unconnected-(BEU1-ERROR#-Pad5)") (class "Default")
      (node (ref "BEU1") (pin "5") (pinfunction "ERROR#_5") (pintype "unspecified+no_connect"))
    )
    (net (code "71") (name "unconnected-(BEU1-SENSE-Pad2)") (class "Default")
      (node (ref "BEU1") (pin "2") (pinfunction "SENSE_2") (pintype "unspecified+no_connect"))
    )
    (net (code "72") (name "unconnected-(BEU1-VTAP-Pad6)") (class "Default")
      (node (ref "BEU1") (pin "6") (pinfunction "VTAP_6") (pintype "unspecified+no_connect"))
    )
    (net (code "73") (name "unconnected-(BFU1-ERROR#-Pad5)") (class "Default")
      (node (ref "BFU1") (pin "5") (pinfunction "ERROR#_5") (pintype "unspecified+no_connect"))
    )
    (net (code "74") (name "unconnected-(BFU1-SENSE-Pad2)") (class "Default")
      (node (ref "BFU1") (pin "2") (pinfunction "SENSE_2") (pintype "unspecified+no_connect"))
    )
    (net (code "75") (name "unconnected-(BFU1-VTAP-Pad6)") (class "Default")
      (node (ref "BFU1") (pin "6") (pinfunction "VTAP_6") (pintype "unspecified+no_connect"))
    )
  )
)
